# UpdatedSch.net
KiCad netlist of a schematic drawn in Altium Designer
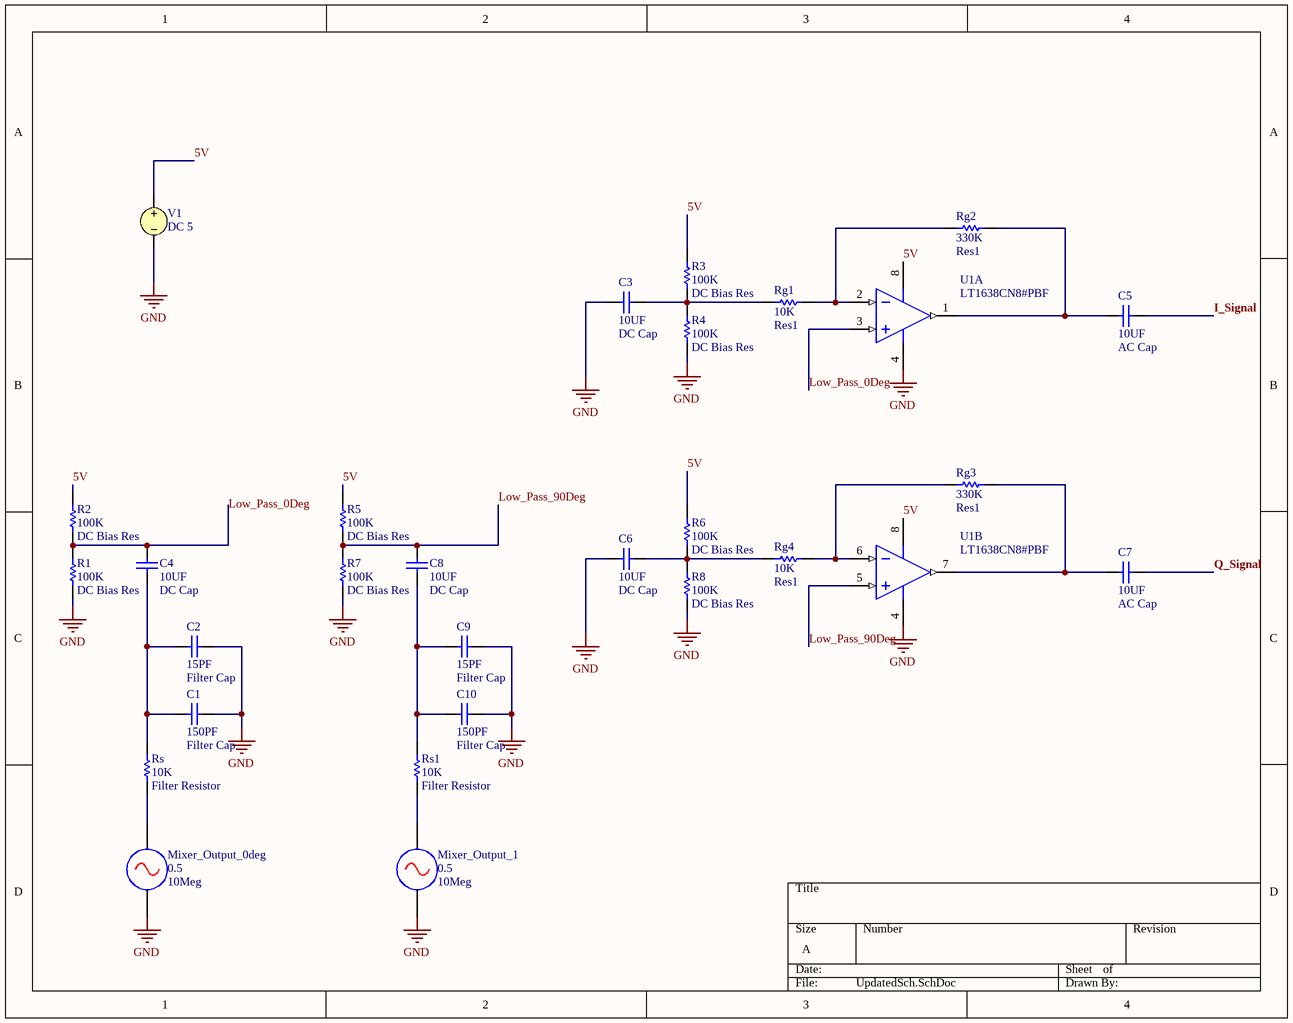
[diagram p0: UpdatedSch.SchDoc]

(export (version "E")
  (design (tool "Eeschema 10.0.6"))
  (components
    (comp (ref "C1")
      (value "Filter Cap")
      (footprint "RADIAL-0.1")
      (description "Capacitor")
      (fields
        (field (name "ALTIUM_VALUE") "150PF")
        (field (name "MANUFACTURER PART NUMBER") "K151J15C0GF53L2")
        (field (name "PUBLISHER") "Altium Limited")
      )
      (libsource (lib "ECE295-Capacitors-TH") (part "CAP CER 150PF 50V C0G/NP0 RADIAL"))
    )
    (comp (ref "C2")
      (value "Filter Cap")
      (footprint "RADIAL-0.1")
      (description "Capacitor")
      (fields
        (field (name "ALTIUM_VALUE") "15PF")
        (field (name "MANUFACTURER PART NUMBER") "K150J15C0GF5TL2")
        (field (name "PUBLISHER") "Altium Limited")
      )
      (libsource (lib "ECE295-Capacitors-TH") (part "CAP CER 15PF 50V C0G/NP0 RADIAL"))
    )
    (comp (ref "C3")
      (value "DC Cap")
      (footprint "RADIAL-0.1")
      (description "Capacitor")
      (fields
        (field (name "ALTIUM_VALUE") "10UF")
        (field (name "MANUFACTURER PART NUMBER") "ESK106M063AC3FA")
        (field (name "PUBLISHER") "Altium Limited")
      )
      (libsource (lib "ECE295-Capacitors-TH") (part "CAP ALUM 10UF 20% 63V RADIAL"))
    )
    (comp (ref "C4")
      (value "DC Cap")
      (footprint "RADIAL-0.1")
      (description "Capacitor")
      (fields
        (field (name "ALTIUM_VALUE") "10UF")
        (field (name "MANUFACTURER PART NUMBER") "ESK106M063AC3FA")
        (field (name "PUBLISHER") "Altium Limited")
      )
      (libsource (lib "ECE295-Capacitors-TH") (part "CAP ALUM 10UF 20% 63V RADIAL"))
    )
    (comp (ref "C5")
      (value "AC Cap")
      (footprint "RADIAL-0.1")
      (description "Capacitor")
      (fields
        (field (name "ALTIUM_VALUE") "10UF")
        (field (name "MANUFACTURER PART NUMBER") "ESK106M063AC3FA")
        (field (name "PUBLISHER") "Altium Limited")
      )
      (libsource (lib "ECE295-Capacitors-TH") (part "CAP ALUM 10UF 20% 63V RADIAL"))
    )
    (comp (ref "C6")
      (value "DC Cap")
      (footprint "RADIAL-0.1")
      (description "Capacitor")
      (fields
        (field (name "ALTIUM_VALUE") "10UF")
        (field (name "MANUFACTURER PART NUMBER") "ESK106M063AC3FA")
        (field (name "PUBLISHER") "Altium Limited")
      )
      (libsource (lib "ECE295-Capacitors-TH") (part "CAP ALUM 10UF 20% 63V RADIAL"))
    )
    (comp (ref "C7")
      (value "AC Cap")
      (footprint "RADIAL-0.1")
      (description "Capacitor")
      (fields
        (field (name "ALTIUM_VALUE") "10UF")
        (field (name "MANUFACTURER PART NUMBER") "ESK106M063AC3FA")
        (field (name "PUBLISHER") "Altium Limited")
      )
      (libsource (lib "ECE295-Capacitors-TH") (part "CAP ALUM 10UF 20% 63V RADIAL"))
    )
    (comp (ref "C8")
      (value "DC Cap")
      (footprint "RADIAL-0.1")
      (description "Capacitor")
      (fields
        (field (name "ALTIUM_VALUE") "10UF")
        (field (name "MANUFACTURER PART NUMBER") "ESK106M063AC3FA")
        (field (name "PUBLISHER") "Altium Limited")
      )
      (libsource (lib "ECE295-Capacitors-TH") (part "CAP ALUM 10UF 20% 63V RADIAL"))
    )
    (comp (ref "C9")
      (value "Filter Cap")
      (footprint "RADIAL-0.1")
      (description "Capacitor")
      (fields
        (field (name "ALTIUM_VALUE") "15PF")
        (field (name "MANUFACTURER PART NUMBER") "K150J15C0GF5TL2")
        (field (name "PUBLISHER") "Altium Limited")
      )
      (libsource (lib "ECE295-Capacitors-TH") (part "CAP CER 15PF 50V C0G/NP0 RADIAL"))
    )
    (comp (ref "C10")
      (value "Filter Cap")
      (footprint "RADIAL-0.1")
      (description "Capacitor")
      (fields
        (field (name "ALTIUM_VALUE") "150PF")
        (field (name "MANUFACTURER PART NUMBER") "K151J15C0GF53L2")
        (field (name "PUBLISHER") "Altium Limited")
      )
      (libsource (lib "ECE295-Capacitors-TH") (part "CAP CER 150PF 50V C0G/NP0 RADIAL"))
    )
    (comp (ref "Mixer_Output_0deg")
      (value "AC Voltage Source")
      (fields (field (name "AMP") "0.5") (field (name "FREQ") "10Meg"))
      (libsource (lib "Simulation Generic Components") (part "AC Voltage Source"))
    )
    (comp (ref "Mixer_Output_1")
      (value "AC Voltage Source")
      (fields (field (name "AMP") "0.5") (field (name "FREQ") "10Meg"))
      (libsource (lib "Simulation Generic Components") (part "AC Voltage Source"))
    )
    (comp (ref "R1")
      (value "DC Bias Res")
      (footprint "AXIAL-0.1-RES")
      (description "Resistor")
      (fields
        (field (name "ALTIUM_VALUE") "100K")
        (field (name "MANUFACTURER PART NUMBER") "CFR-25JB-52-100K")
        (field (name "TOLERANCE") "0.05")
        (field (name "PUBLISHER") "Altium Limited")
      )
      (libsource (lib "ECE295-Resistors-TH") (part "RES 100K OHM 5% 1/4W AXIAL"))
    )
    (comp (ref "R2")
      (value "DC Bias Res")
      (footprint "AXIAL-0.1-RES")
      (description "Resistor")
      (fields
        (field (name "ALTIUM_VALUE") "100K")
        (field (name "MANUFACTURER PART NUMBER") "CFR-25JB-52-100K")
        (field (name "TOLERANCE") "0.05")
        (field (name "PUBLISHER") "Altium Limited")
      )
      (libsource (lib "ECE295-Resistors-TH") (part "RES 100K OHM 5% 1/4W AXIAL"))
    )
    (comp (ref "R3")
      (value "DC Bias Res")
      (footprint "AXIAL-0.1-RES")
      (description "Resistor")
      (fields
        (field (name "ALTIUM_VALUE") "100K")
        (field (name "MANUFACTURER PART NUMBER") "CFR-25JB-52-100K")
        (field (name "TOLERANCE") "0.05")
        (field (name "PUBLISHER") "Altium Limited")
      )
      (libsource (lib "ECE295-Resistors-TH") (part "RES 100K OHM 5% 1/4W AXIAL"))
    )
    (comp (ref "R4")
      (value "DC Bias Res")
      (footprint "AXIAL-0.1-RES")
      (description "Resistor")
      (fields
        (field (name "ALTIUM_VALUE") "100K")
        (field (name "MANUFACTURER PART NUMBER") "CFR-25JB-52-100K")
        (field (name "TOLERANCE") "0.05")
        (field (name "PUBLISHER") "Altium Limited")
      )
      (libsource (lib "ECE295-Resistors-TH") (part "RES 100K OHM 5% 1/4W AXIAL"))
    )
    (comp (ref "R5")
      (value "DC Bias Res")
      (footprint "AXIAL-0.1-RES")
      (description "Resistor")
      (fields
        (field (name "ALTIUM_VALUE") "100K")
        (field (name "MANUFACTURER PART NUMBER") "CFR-25JB-52-100K")
        (field (name "TOLERANCE") "0.05")
        (field (name "PUBLISHER") "Altium Limited")
      )
      (libsource (lib "ECE295-Resistors-TH") (part "RES 100K OHM 5% 1/4W AXIAL"))
    )
    (comp (ref "R6")
      (value "DC Bias Res")
      (footprint "AXIAL-0.1-RES")
      (description "Resistor")
      (fields
        (field (name "ALTIUM_VALUE") "100K")
        (field (name "MANUFACTURER PART NUMBER") "CFR-25JB-52-100K")
        (field (name "TOLERANCE") "0.05")
        (field (name "PUBLISHER") "Altium Limited")
      )
      (libsource (lib "ECE295-Resistors-TH") (part "RES 100K OHM 5% 1/4W AXIAL"))
    )
    (comp (ref "R7")
      (value "DC Bias Res")
      (footprint "AXIAL-0.1-RES")
      (description "Resistor")
      (fields
        (field (name "ALTIUM_VALUE") "100K")
        (field (name "MANUFACTURER PART NUMBER") "CFR-25JB-52-100K")
        (field (name "TOLERANCE") "0.05")
        (field (name "PUBLISHER") "Altium Limited")
      )
      (libsource (lib "ECE295-Resistors-TH") (part "RES 100K OHM 5% 1/4W AXIAL"))
    )
    (comp (ref "R8")
      (value "DC Bias Res")
      (footprint "AXIAL-0.1-RES")
      (description "Resistor")
      (fields
        (field (name "ALTIUM_VALUE") "100K")
        (field (name "MANUFACTURER PART NUMBER") "CFR-25JB-52-100K")
        (field (name "TOLERANCE") "0.05")
        (field (name "PUBLISHER") "Altium Limited")
      )
      (libsource (lib "ECE295-Resistors-TH") (part "RES 100K OHM 5% 1/4W AXIAL"))
    )
    (comp (ref "Rg1")
      (value "Res1")
      (footprint "AXIAL-0.1-RES")
      (description "Resistor")
      (fields
        (field (name "ALTIUM_VALUE") "10K")
        (field (name "MANUFACTURER PART NUMBER") "CFR-25JB-52-10K")
        (field (name "TOLERANCE") "0.05")
        (field (name "PUBLISHER") "Altium Limited")
      )
      (libsource (lib "ECE295-Resistors-TH") (part "RES 10K OHM 5% 1/4W AXIAL"))
    )
    (comp (ref "Rg2")
      (value "Res1")
      (footprint "AXIAL-0.1-RES")
      (description "Resistor")
      (fields
        (field (name "ALTIUM_VALUE") "330K")
        (field (name "MANUFACTURER PART NUMBER") "CFR-25JB-52-330K")
        (field (name "TOLERANCE") "0.05")
        (field (name "PUBLISHER") "Altium Limited")
      )
      (libsource (lib "ECE295-Resistors-TH") (part "RES 330K OHM 5% 1/4W AXIAL"))
    )
    (comp (ref "Rg3")
      (value "Res1")
      (footprint "AXIAL-0.1-RES")
      (description "Resistor")
      (fields
        (field (name "ALTIUM_VALUE") "330K")
        (field (name "MANUFACTURER PART NUMBER") "CFR-25JB-52-330K")
        (field (name "TOLERANCE") "0.05")
        (field (name "PUBLISHER") "Altium Limited")
      )
      (libsource (lib "ECE295-Resistors-TH") (part "RES 330K OHM 5% 1/4W AXIAL"))
    )
    (comp (ref "Rg4")
      (value "Res1")
      (footprint "AXIAL-0.1-RES")
      (description "Resistor")
      (fields
        (field (name "ALTIUM_VALUE") "10K")
        (field (name "MANUFACTURER PART NUMBER") "CFR-25JB-52-10K")
        (field (name "TOLERANCE") "0.05")
        (field (name "PUBLISHER") "Altium Limited")
      )
      (libsource (lib "ECE295-Resistors-TH") (part "RES 10K OHM 5% 1/4W AXIAL"))
    )
    (comp (ref "Rs")
      (value "Filter Resistor")
      (footprint "AXIAL-0.1-RES")
      (description "Resistor")
      (fields
        (field (name "ALTIUM_VALUE") "10K")
        (field (name "MANUFACTURER PART NUMBER") "CFR-25JB-52-10K")
        (field (name "TOLERANCE") "0.05")
        (field (name "PUBLISHER") "Altium Limited")
      )
      (libsource (lib "ECE295-Resistors-TH") (part "RES 10K OHM 5% 1/4W AXIAL"))
    )
    (comp (ref "Rs1")
      (value "Filter Resistor")
      (footprint "AXIAL-0.1-RES")
      (description "Resistor")
      (fields
        (field (name "ALTIUM_VALUE") "10K")
        (field (name "MANUFACTURER PART NUMBER") "CFR-25JB-52-10K")
        (field (name "TOLERANCE") "0.05")
        (field (name "PUBLISHER") "Altium Limited")
      )
      (libsource (lib "ECE295-Resistors-TH") (part "RES 10K OHM 5% 1/4W AXIAL"))
    )
    (comp (ref "U1")
      (value "LT1638CN8#PBF")
      (footprint "LT-N8-8")
      (fields
        (field (name "MANUFACTURER") "Linear Technology")
        (field (name "LINEAR TECHNOLOGY PART NUMBER") "LT1638")
      )
      (libsource (lib "Altium Content Vault") (part "LT-LT1638-N8-8"))
    )
    (comp (ref "V1")
      (value "DC 5")
      (description "Voltage Source")
      (fields (field (name "PUBLISHER") "Altium Limited"))
      (libsource (lib "Simulation Generic Components") (part "VSRC"))
    )
  )
  (nets
    (net (code "1") (name "/5V") (class "Default")
      (node (ref "R2") (pin "2") (pinfunction "2_2") (pintype "passive"))
      (node (ref "R3") (pin "2") (pinfunction "2_2") (pintype "passive"))
      (node (ref "R5") (pin "2") (pinfunction "2_2") (pintype "passive"))
      (node (ref "R6") (pin "2") (pinfunction "2_2") (pintype "passive"))
      (node (ref "U1") (pin "8") (pinfunction "V+_8") (pintype "power_in"))
      (node (ref "V1") (pin "1") (pinfunction "1_1") (pintype "passive"))
    )
    (net (code "2") (name "/I_Signal") (class "Default")
      (node (ref "C5") (pin "1") (pinfunction "1_1") (pintype "passive"))
    )
    (net (code "3") (name "/Low_Pass_0Deg") (class "Default")
      (node (ref "C4") (pin "2") (pinfunction "2_2") (pintype "passive"))
      (node (ref "R1") (pin "2") (pinfunction "2_2") (pintype "passive"))
      (node (ref "R2") (pin "1") (pinfunction "1_1") (pintype "passive"))
      (node (ref "U1") (pin "3") (pinfunction "+IN_A_3") (pintype "input"))
    )
    (net (code "4") (name "/Low_Pass_90Deg") (class "Default")
      (node (ref "C8") (pin "2") (pinfunction "2_2") (pintype "passive"))
      (node (ref "R5") (pin "1") (pinfunction "1_1") (pintype "passive"))
      (node (ref "R7") (pin "2") (pinfunction "2_2") (pintype "passive"))
      (node (ref "U1") (pin "5") (pinfunction "+IN_B_5") (pintype "input"))
    )
    (net (code "5") (name "/Q_Signal") (class "Default")
      (node (ref "C7") (pin "1") (pinfunction "1_1") (pintype "passive"))
    )
    (net (code "6") (name "GND") (class "Default")
      (node (ref "C1") (pin "2") (pinfunction "2_2") (pintype "passive"))
      (node (ref "C10") (pin "2") (pinfunction "2_2") (pintype "passive"))
      (node (ref "C2") (pin "2") (pinfunction "2_2") (pintype "passive"))
      (node (ref "C3") (pin "2") (pinfunction "2_2") (pintype "passive"))
      (node (ref "C6") (pin "2") (pinfunction "2_2") (pintype "passive"))
      (node (ref "C9") (pin "2") (pinfunction "2_2") (pintype "passive"))
      (node (ref "Mixer_Output_0deg") (pin "2") (pinfunction "2_2") (pintype "passive"))
      (node (ref "Mixer_Output_1") (pin "2") (pinfunction "2_2") (pintype "passive"))
      (node (ref "R1") (pin "1") (pinfunction "1_1") (pintype "passive"))
      (node (ref "R4") (pin "1") (pinfunction "1_1") (pintype "passive"))
      (node (ref "R7") (pin "1") (pinfunction "1_1") (pintype "passive"))
      (node (ref "R8") (pin "1") (pinfunction "1_1") (pintype "passive"))
      (node (ref "U1") (pin "4") (pinfunction "V-_4") (pintype "power_in"))
      (node (ref "V1") (pin "2") (pinfunction "2_2") (pintype "passive"))
    )
    (net (code "7") (name "Net-(C1-Pad1)") (class "Default")
      (node (ref "C1") (pin "1") (pinfunction "1_1") (pintype "passive"))
      (node (ref "C2") (pin "1") (pinfunction "1_1") (pintype "passive"))
      (node (ref "C4") (pin "1") (pinfunction "1_1") (pintype "passive"))
      (node (ref "Rs") (pin "2") (pinfunction "2_2") (pintype "passive"))
    )
    (net (code "8") (name "Net-(C3-Pad1)") (class "Default")
      (node (ref "C3") (pin "1") (pinfunction "1_1") (pintype "passive"))
      (node (ref "R3") (pin "1") (pinfunction "1_1") (pintype "passive"))
      (node (ref "R4") (pin "2") (pinfunction "2_2") (pintype "passive"))
      (node (ref "Rg1") (pin "1") (pinfunction "1_1") (pintype "passive"))
    )
    (net (code "9") (name "Net-(C6-Pad1)") (class "Default")
      (node (ref "C6") (pin "1") (pinfunction "1_1") (pintype "passive"))
      (node (ref "R6") (pin "1") (pinfunction "1_1") (pintype "passive"))
      (node (ref "R8") (pin "2") (pinfunction "2_2") (pintype "passive"))
      (node (ref "Rg4") (pin "1") (pinfunction "1_1") (pintype "passive"))
    )
    (net (code "10") (name "Net-(C10-Pad1)") (class "Default")
      (node (ref "C10") (pin "1") (pinfunction "1_1") (pintype "passive"))
      (node (ref "C8") (pin "1") (pinfunction "1_1") (pintype "passive"))
      (node (ref "C9") (pin "1") (pinfunction "1_1") (pintype "passive"))
      (node (ref "Rs1") (pin "2") (pinfunction "2_2") (pintype "passive"))
    )
    (net (code "11") (name "Net-(Mixer_Output_0deg-Pad1)") (class "Default")
      (node (ref "Mixer_Output_0deg") (pin "1") (pinfunction "1_1") (pintype "passive"))
      (node (ref "Rs") (pin "1") (pinfunction "1_1") (pintype "passive"))
    )
    (net (code "12") (name "Net-(Mixer_Output_1-Pad1)") (class "Default")
      (node (ref "Mixer_Output_1") (pin "1") (pinfunction "1_1") (pintype "passive"))
      (node (ref "Rs1") (pin "1") (pinfunction "1_1") (pintype "passive"))
    )
    (net (code "13") (name "Net-(U1A--IN_A)") (class "Default")
      (node (ref "Rg1") (pin "2") (pinfunction "2_2") (pintype "passive"))
      (node (ref "Rg2") (pin "1") (pinfunction "1_1") (pintype "passive"))
      (node (ref "U1") (pin "2") (pinfunction "-IN_A_2") (pintype "input"))
    )
    (net (code "14") (name "Net-(U1A-OUT_A)") (class "Default")
      (node (ref "C5") (pin "2") (pinfunction "2_2") (pintype "passive"))
      (node (ref "Rg2") (pin "2") (pinfunction "2_2") (pintype "passive"))
      (node (ref "U1") (pin "1") (pinfunction "OUT_A_1") (pintype "output"))
    )
    (net (code "15") (name "Net-(U1B--IN_B)") (class "Default")
      (node (ref "Rg3") (pin "1") (pinfunction "1_1") (pintype "passive"))
      (node (ref "Rg4") (pin "2") (pinfunction "2_2") (pintype "passive"))
      (node (ref "U1") (pin "6") (pinfunction "-IN_B_6") (pintype "input"))
    )
    (net (code "16") (name "Net-(U1B-OUT_B)") (class "Default")
      (node (ref "C7") (pin "2") (pinfunction "2_2") (pintype "passive"))
      (node (ref "Rg3") (pin "2") (pinfunction "2_2") (pintype "passive"))
      (node (ref "U1") (pin "7") (pinfunction "OUT_B_7") (pintype "output"))
    )
  )
)
